# Main.net
KiCad netlist of a schematic drawn in Altium Designer
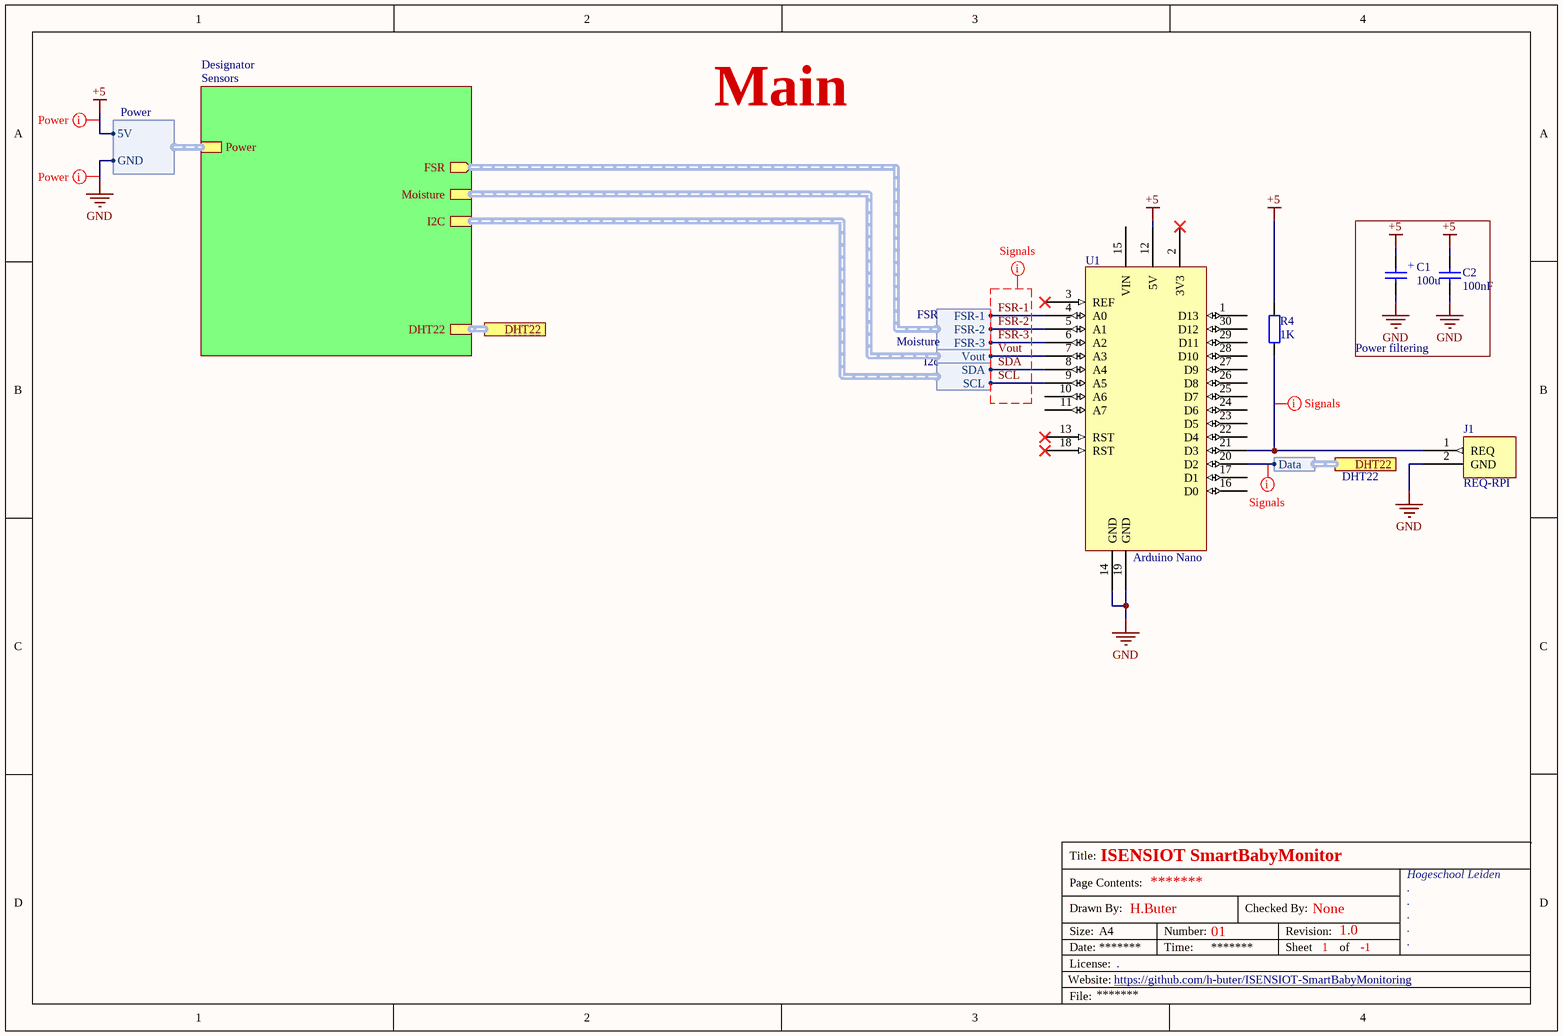
[diagram p0: Main.SchDoc]

(export (version "E")
  (design (tool "Eeschema 10.0.6"))
  (components
    (comp (ref "C1")
      (value "100u")
      (footprint "Cap 100uF 16V 5x12mm")
      (description "Cap 100uF 16V 5x12mm")
      (libsource (lib "ISENSIOT") (part "Cap 100uF 16V 5x12mm"))
    )
    (comp (ref "C2")
      (value "100nF")
      (footprint "C1206")
      (description "SMD Capacitor 1206")
      (fields (field (name "PUBLISHER") "Windesheim"))
      (libsource (lib "WindesheimLibrary_v5") (part "Capacitor_1206"))
    )
    (comp (ref "J1")
      (value "REQ-RPI")
      (footprint "JST-XH 2pin")
      (description "Request connection to Raspberry Pi")
      (libsource (lib "ISENSIOT") (part "REQ-RPI"))
    )
    (comp (ref "R4")
      (value "1K")
      (footprint "R1206")
      (description "SMD Resistor 1206")
      (fields (field (name "PUBLISHER") "Windesheim"))
      (libsource (lib "WindesheimLibrary_v5") (part "Resistor_1206"))
    )
    (comp (ref "U1")
      (value "Arduino Nano")
      (footprint "Arduino Nano")
      (libsource (lib "ISENSIOT") (part "Arduino Nano"))
    )
  )
  (nets
    (net (code "5") (name "+5") (class "Default")
      (node (ref "C1") (pin "1") (pinfunction "1_1") (pintype "passive"))
      (node (ref "C2") (pin "2") (pinfunction "2_2") (pintype "passive"))
      (node (ref "R4") (pin "2") (pinfunction "2_2") (pintype "passive"))
      (node (ref "U1") (pin "12") (pinfunction "5V_12") (pintype "power_in"))
    )
    (net (code "6") (name "/Data") (class "Default")
      (node (ref "U1") (pin "20") (pinfunction "D2_20") (pintype "bidirectional"))
    )
    (net (code "7") (name "/FSR-1") (class "Default")
      (node (ref "U1") (pin "4") (pinfunction "A0_4") (pintype "bidirectional"))
    )
    (net (code "8") (name "/FSR-2") (class "Default")
      (node (ref "U1") (pin "5") (pinfunction "A1_5") (pintype "bidirectional"))
    )
    (net (code "9") (name "/FSR-3") (class "Default")
      (node (ref "U1") (pin "6") (pinfunction "A2_6") (pintype "bidirectional"))
    )
    (net (code "11") (name "/SCL") (class "Default")
      (node (ref "U1") (pin "9") (pinfunction "A5_9") (pintype "bidirectional"))
    )
    (net (code "12") (name "/SDA") (class "Default")
      (node (ref "U1") (pin "8") (pinfunction "A4_8") (pintype "bidirectional"))
    )
    (net (code "13") (name "/Vout") (class "Default")
      (node (ref "U1") (pin "7") (pinfunction "A3_7") (pintype "bidirectional"))
    )
    (net (code "18") (name "GND") (class "Default")
      (node (ref "C1") (pin "2") (pinfunction "2_2") (pintype "passive"))
      (node (ref "C2") (pin "1") (pinfunction "1_1") (pintype "passive"))
      (node (ref "J1") (pin "2") (pinfunction "GND_2") (pintype "power_in"))
      (node (ref "U1") (pin "14") (pinfunction "GND_14") (pintype "power_in"))
      (node (ref "U1") (pin "19") (pinfunction "GND_19") (pintype "power_in"))
    )
    (net (code "19") (name "Net-(J1-REQ)") (class "Default")
      (node (ref "J1") (pin "1") (pinfunction "REQ_1") (pintype "output"))
      (node (ref "R4") (pin "1") (pinfunction "1_1") (pintype "passive"))
      (node (ref "U1") (pin "21") (pinfunction "D3_21") (pintype "bidirectional"))
    )
    (net (code "20") (name "unconnected-(U1-3V3-Pad2)") (class "Default")
      (node (ref "U1") (pin "2") (pinfunction "3V3_2") (pintype "power_in+no_connect"))
    )
    (net (code "21") (name "unconnected-(U1-A6-Pad10)") (class "Default")
      (node (ref "U1") (pin "10") (pinfunction "A6_10") (pintype "bidirectional"))
    )
    (net (code "22") (name "unconnected-(U1-A7-Pad11)") (class "Default")
      (node (ref "U1") (pin "11") (pinfunction "A7_11") (pintype "bidirectional"))
    )
    (net (code "23") (name "unconnected-(U1-D0-Pad16)") (class "Default")
      (node (ref "U1") (pin "16") (pinfunction "D0_16") (pintype "bidirectional"))
    )
    (net (code "24") (name "unconnected-(U1-D1-Pad17)") (class "Default")
      (node (ref "U1") (pin "17") (pinfunction "D1_17") (pintype "bidirectional"))
    )
    (net (code "25") (name "unconnected-(U1-D4-Pad22)") (class "Default")
      (node (ref "U1") (pin "22") (pinfunction "D4_22") (pintype "bidirectional"))
    )
    (net (code "26") (name "unconnected-(U1-D5-Pad23)") (class "Default")
      (node (ref "U1") (pin "23") (pinfunction "D5_23") (pintype "bidirectional"))
    )
    (net (code "27") (name "unconnected-(U1-D6-Pad24)") (class "Default")
      (node (ref "U1") (pin "24") (pinfunction "D6_24") (pintype "bidirectional"))
    )
    (net (code "28") (name "unconnected-(U1-D7-Pad25)") (class "Default")
      (node (ref "U1") (pin "25") (pinfunction "D7_25") (pintype "bidirectional"))
    )
    (net (code "29") (name "unconnected-(U1-D8-Pad26)") (class "Default")
      (node (ref "U1") (pin "26") (pinfunction "D8_26") (pintype "bidirectional"))
    )
    (net (code "30") (name "unconnected-(U1-D9-Pad27)") (class "Default")
      (node (ref "U1") (pin "27") (pinfunction "D9_27") (pintype "bidirectional"))
    )
    (net (code "31") (name "unconnected-(U1-D10-Pad28)") (class "Default")
      (node (ref "U1") (pin "28") (pinfunction "D10_28") (pintype "bidirectional"))
    )
    (net (code "32") (name "unconnected-(U1-D11-Pad29)") (class "Default")
      (node (ref "U1") (pin "29") (pinfunction "D11_29") (pintype "bidirectional"))
    )
    (net (code "33") (name "unconnected-(U1-D12-Pad30)") (class "Default")
      (node (ref "U1") (pin "30") (pinfunction "D12_30") (pintype "bidirectional"))
    )
    (net (code "34") (name "unconnected-(U1-D13-Pad1)") (class "Default")
      (node (ref "U1") (pin "1") (pinfunction "D13_1") (pintype "bidirectional"))
    )
    (net (code "35") (name "unconnected-(U1-REF-Pad3)") (class "Default")
      (node (ref "U1") (pin "3") (pinfunction "REF_3") (pintype "input+no_connect"))
    )
    (net (code "36") (name "unconnected-(U1-RST-Pad13)") (class "Default")
      (node (ref "U1") (pin "13") (pinfunction "RST_13") (pintype "input+no_connect"))
    )
    (net (code "37") (name "unconnected-(U1-RST-Pad18)") (class "Default")
      (node (ref "U1") (pin "18") (pinfunction "RST_18") (pintype "input+no_connect"))
    )
    (net (code "38") (name "unconnected-(U1-VIN-Pad15)") (class "Default")
      (node (ref "U1") (pin "15") (pinfunction "VIN_15") (pintype "power_in"))
    )
  )
)
